# Uebersicht.net
KiCad netlist of a schematic drawn in Altium Designer
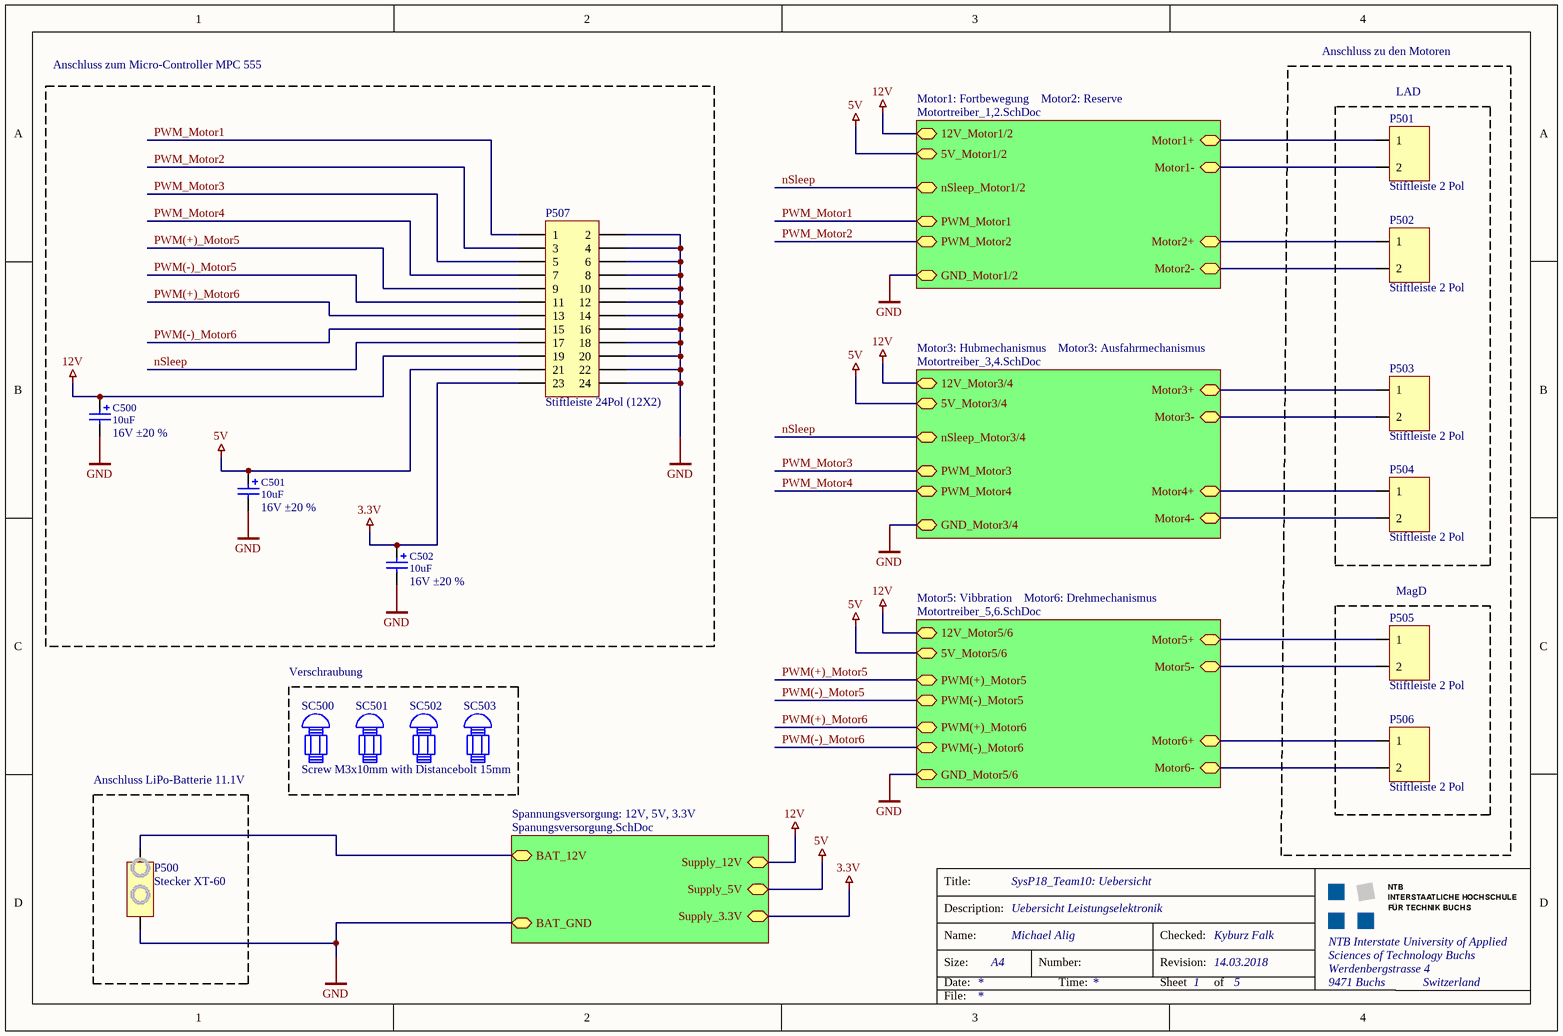
[diagram p0: Uebersicht.SchDoc]

(export (version "E")
  (design (tool "Eeschema 10.0.6"))
  (components
    (comp (ref "C500")
      (value "10uF")
      (footprint "CDE_CAP AVE CODE D_H")
      (description "Aluminum Electrolytic Capacitors for Filtering and Bypass, 47uF, 16V")
      (fields
        (field (name "MANUFACTURER") "Cornell Dubilier")
        (field (name "VALUEADDON") "16V ±20 %")
        (field (name "Comment") "AVE476M16D16T-F")
        (field (name "PUBLISHER") "Stefan Ursella, M.Eng")
      )
      (libsource (lib "Motorentreiber") (part "CDE_AVE476M16D16T-F_AVE CODE D"))
    )
    (comp (ref "C501")
      (value "10uF")
      (footprint "CDE_CAP AVE CODE D_H")
      (description "Aluminum Electrolytic Capacitors for Filtering and Bypass, 47uF, 16V")
      (fields
        (field (name "MANUFACTURER") "Cornell Dubilier")
        (field (name "VALUEADDON") "16V ±20 %")
        (field (name "Comment") "AVE476M16D16T-F")
        (field (name "PUBLISHER") "Stefan Ursella, M.Eng")
      )
      (libsource (lib "Motorentreiber") (part "CDE_AVE476M16D16T-F_AVE CODE D"))
    )
    (comp (ref "C502")
      (value "10uF")
      (footprint "CDE_CAP AVE CODE D_H")
      (description "Aluminum Electrolytic Capacitors for Filtering and Bypass, 47uF, 16V")
      (fields
        (field (name "MANUFACTURER") "Cornell Dubilier")
        (field (name "VALUEADDON") "16V ±20 %")
        (field (name "Comment") "AVE476M16D16T-F")
        (field (name "PUBLISHER") "Stefan Ursella, M.Eng")
      )
      (libsource (lib "Motorentreiber") (part "CDE_AVE476M16D16T-F_AVE CODE D"))
    )
    (comp (ref "P500")
      (value "Stecker XT-60")
      (footprint "Batteriestecker XT-60")
      (libsource (lib "Schemasymbole") (part "Batteriestecker XT-60"))
    )
    (comp (ref "P501")
      (value "Stiftleiste 2 Pol")
      (footprint "2Pin Header 2.54mm")
      (description "2 Pin Header 2.54mm")
      (libsource (lib "Motorentreiber") (part "2 Pin Connector"))
    )
    (comp (ref "P502")
      (value "Stiftleiste 2 Pol")
      (footprint "2Pin Header 2.54mm")
      (description "2 Pin Header 2.54mm")
      (libsource (lib "Motorentreiber") (part "2 Pin Connector"))
    )
    (comp (ref "P503")
      (value "Stiftleiste 2 Pol")
      (footprint "2Pin Header 2.54mm")
      (description "2 Pin Header 2.54mm")
      (libsource (lib "Motorentreiber") (part "2 Pin Connector"))
    )
    (comp (ref "P504")
      (value "Stiftleiste 2 Pol")
      (footprint "2Pin Header 2.54mm")
      (description "2 Pin Header 2.54mm")
      (libsource (lib "Motorentreiber") (part "2 Pin Connector"))
    )
    (comp (ref "P505")
      (value "Stiftleiste 2 Pol")
      (footprint "2Pin Header 2.54mm")
      (description "2 Pin Header 2.54mm")
      (libsource (lib "Motorentreiber") (part "2 Pin Connector"))
    )
    (comp (ref "P506")
      (value "Stiftleiste 2 Pol")
      (footprint "2Pin Header 2.54mm")
      (description "2 Pin Header 2.54mm")
      (libsource (lib "Motorentreiber") (part "2 Pin Connector"))
    )
    (comp (ref "P507")
      (value "Stiftleiste 24Pol (12X2)")
      (footprint "HDR2X12")
      (description "Header, 12-Pin, Dual row")
      (fields (field (name "PUBLISHER") "Altium Limited"))
      (libsource (lib "Miscellaneous Connectors") (part "Header 12X2"))
    )
    (comp (ref "SC500")
      (value "Screw M3x10mm with Distancebolt 15mm")
      (footprint "Screw_M3x10_Dist_15mm")
      (libsource (lib "Motorentreiber") (part "Screw M3 10mm with Distancebolt 15mm"))
    )
    (comp (ref "SC501")
      (value "Screw M3x10mm with Distancebolt 15mm")
      (footprint "Screw_M3x10_Dist_15mm")
      (libsource (lib "Motorentreiber") (part "Screw M3 10mm with Distancebolt 15mm"))
    )
    (comp (ref "SC502")
      (value "Screw M3x10mm with Distancebolt 15mm")
      (footprint "Screw_M3x10_Dist_15mm")
      (libsource (lib "Motorentreiber") (part "Screw M3 10mm with Distancebolt 15mm"))
    )
    (comp (ref "SC503")
      (value "Screw M3x10mm with Distancebolt 15mm")
      (footprint "Screw_M3x10_Dist_15mm")
      (libsource (lib "Motorentreiber") (part "Screw M3 10mm with Distancebolt 15mm"))
    )
  )
  (nets
    (net (code "1") (name "/BAT_12V") (class "Default")
      (node (ref "P500") (pin "2") (pinfunction "2_2") (pintype "passive"))
    )
    (net (code "2") (name "/Motor1+") (class "Default")
      (node (ref "P501") (pin "1") (pinfunction "1_1") (pintype "passive"))
    )
    (net (code "3") (name "/Motor1-") (class "Default")
      (node (ref "P501") (pin "2") (pinfunction "2_2") (pintype "passive"))
    )
    (net (code "4") (name "/Motor2+") (class "Default")
      (node (ref "P502") (pin "1") (pinfunction "1_1") (pintype "passive"))
    )
    (net (code "5") (name "/Motor2-") (class "Default")
      (node (ref "P502") (pin "2") (pinfunction "2_2") (pintype "passive"))
    )
    (net (code "6") (name "/Motor3+") (class "Default")
      (node (ref "P503") (pin "1") (pinfunction "1_1") (pintype "passive"))
    )
    (net (code "7") (name "/Motor3-") (class "Default")
      (node (ref "P503") (pin "2") (pinfunction "2_2") (pintype "passive"))
    )
    (net (code "8") (name "/Motor4+") (class "Default")
      (node (ref "P504") (pin "1") (pinfunction "1_1") (pintype "passive"))
    )
    (net (code "9") (name "/Motor4-") (class "Default")
      (node (ref "P504") (pin "2") (pinfunction "2_2") (pintype "passive"))
    )
    (net (code "10") (name "/Motor5+") (class "Default")
      (node (ref "P505") (pin "1") (pinfunction "1_1") (pintype "passive"))
    )
    (net (code "11") (name "/Motor5-") (class "Default")
      (node (ref "P505") (pin "2") (pinfunction "2_2") (pintype "passive"))
    )
    (net (code "12") (name "/Motor6+") (class "Default")
      (node (ref "P506") (pin "1") (pinfunction "1_1") (pintype "passive"))
    )
    (net (code "13") (name "/Motor6-") (class "Default")
      (node (ref "P506") (pin "2") (pinfunction "2_2") (pintype "passive"))
    )
    (net (code "14") (name "/PWM(+)_Motor5") (class "Default")
      (node (ref "P507") (pin "9") (pinfunction "9_9") (pintype "passive"))
    )
    (net (code "15") (name "/PWM(+)_Motor6") (class "Default")
      (node (ref "P507") (pin "13") (pinfunction "13_13") (pintype "passive"))
    )
    (net (code "16") (name "/PWM(-)_Motor5") (class "Default")
      (node (ref "P507") (pin "11") (pinfunction "11_11") (pintype "passive"))
    )
    (net (code "17") (name "/PWM(-)_Motor6") (class "Default")
      (node (ref "P507") (pin "15") (pinfunction "15_15") (pintype "passive"))
    )
    (net (code "18") (name "/PWM_Motor1") (class "Default")
      (node (ref "P507") (pin "1") (pinfunction "1_1") (pintype "passive"))
    )
    (net (code "19") (name "/PWM_Motor2") (class "Default")
      (node (ref "P507") (pin "3") (pinfunction "3_3") (pintype "passive"))
    )
    (net (code "20") (name "/PWM_Motor3") (class "Default")
      (node (ref "P507") (pin "5") (pinfunction "5_5") (pintype "passive"))
    )
    (net (code "21") (name "/PWM_Motor4") (class "Default")
      (node (ref "P507") (pin "7") (pinfunction "7_7") (pintype "passive"))
    )
    (net (code "22") (name "/nSleep") (class "Default")
      (node (ref "P507") (pin "17") (pinfunction "17_17") (pintype "passive"))
    )
    (net (code "23") (name "3.3V") (class "Default")
      (node (ref "C502") (pin "1") (pinfunction "Pos_1") (pintype "passive"))
      (node (ref "P507") (pin "23") (pinfunction "23_23") (pintype "passive"))
    )
    (net (code "24") (name "5V") (class "Default")
      (node (ref "C501") (pin "1") (pinfunction "Pos_1") (pintype "passive"))
      (node (ref "P507") (pin "21") (pinfunction "21_21") (pintype "passive"))
    )
    (net (code "25") (name "12V") (class "Default")
      (node (ref "C500") (pin "1") (pinfunction "Pos_1") (pintype "passive"))
      (node (ref "P507") (pin "19") (pinfunction "19_19") (pintype "passive"))
    )
    (net (code "26") (name "GND") (class "Default")
      (node (ref "C500") (pin "2") (pinfunction "Neg_2") (pintype "passive"))
      (node (ref "C501") (pin "2") (pinfunction "Neg_2") (pintype "passive"))
      (node (ref "C502") (pin "2") (pinfunction "Neg_2") (pintype "passive"))
      (node (ref "P500") (pin "1") (pinfunction "1_1") (pintype "passive"))
      (node (ref "P507") (pin "10") (pinfunction "10_10") (pintype "passive"))
      (node (ref "P507") (pin "12") (pinfunction "12_12") (pintype "passive"))
      (node (ref "P507") (pin "14") (pinfunction "14_14") (pintype "passive"))
      (node (ref "P507") (pin "16") (pinfunction "16_16") (pintype "passive"))
      (node (ref "P507") (pin "18") (pinfunction "18_18") (pintype "passive"))
      (node (ref "P507") (pin "2") (pinfunction "2_2") (pintype "passive"))
      (node (ref "P507") (pin "20") (pinfunction "20_20") (pintype "passive"))
      (node (ref "P507") (pin "22") (pinfunction "22_22") (pintype "passive"))
      (node (ref "P507") (pin "24") (pinfunction "24_24") (pintype "passive"))
      (node (ref "P507") (pin "4") (pinfunction "4_4") (pintype "passive"))
      (node (ref "P507") (pin "6") (pinfunction "6_6") (pintype "passive"))
      (node (ref "P507") (pin "8") (pinfunction "8_8") (pintype "passive"))
    )
  )
)
